# GBprinter-D1-Shield-EXT.net
KiCad netlist of a schematic drawn in EAGLE
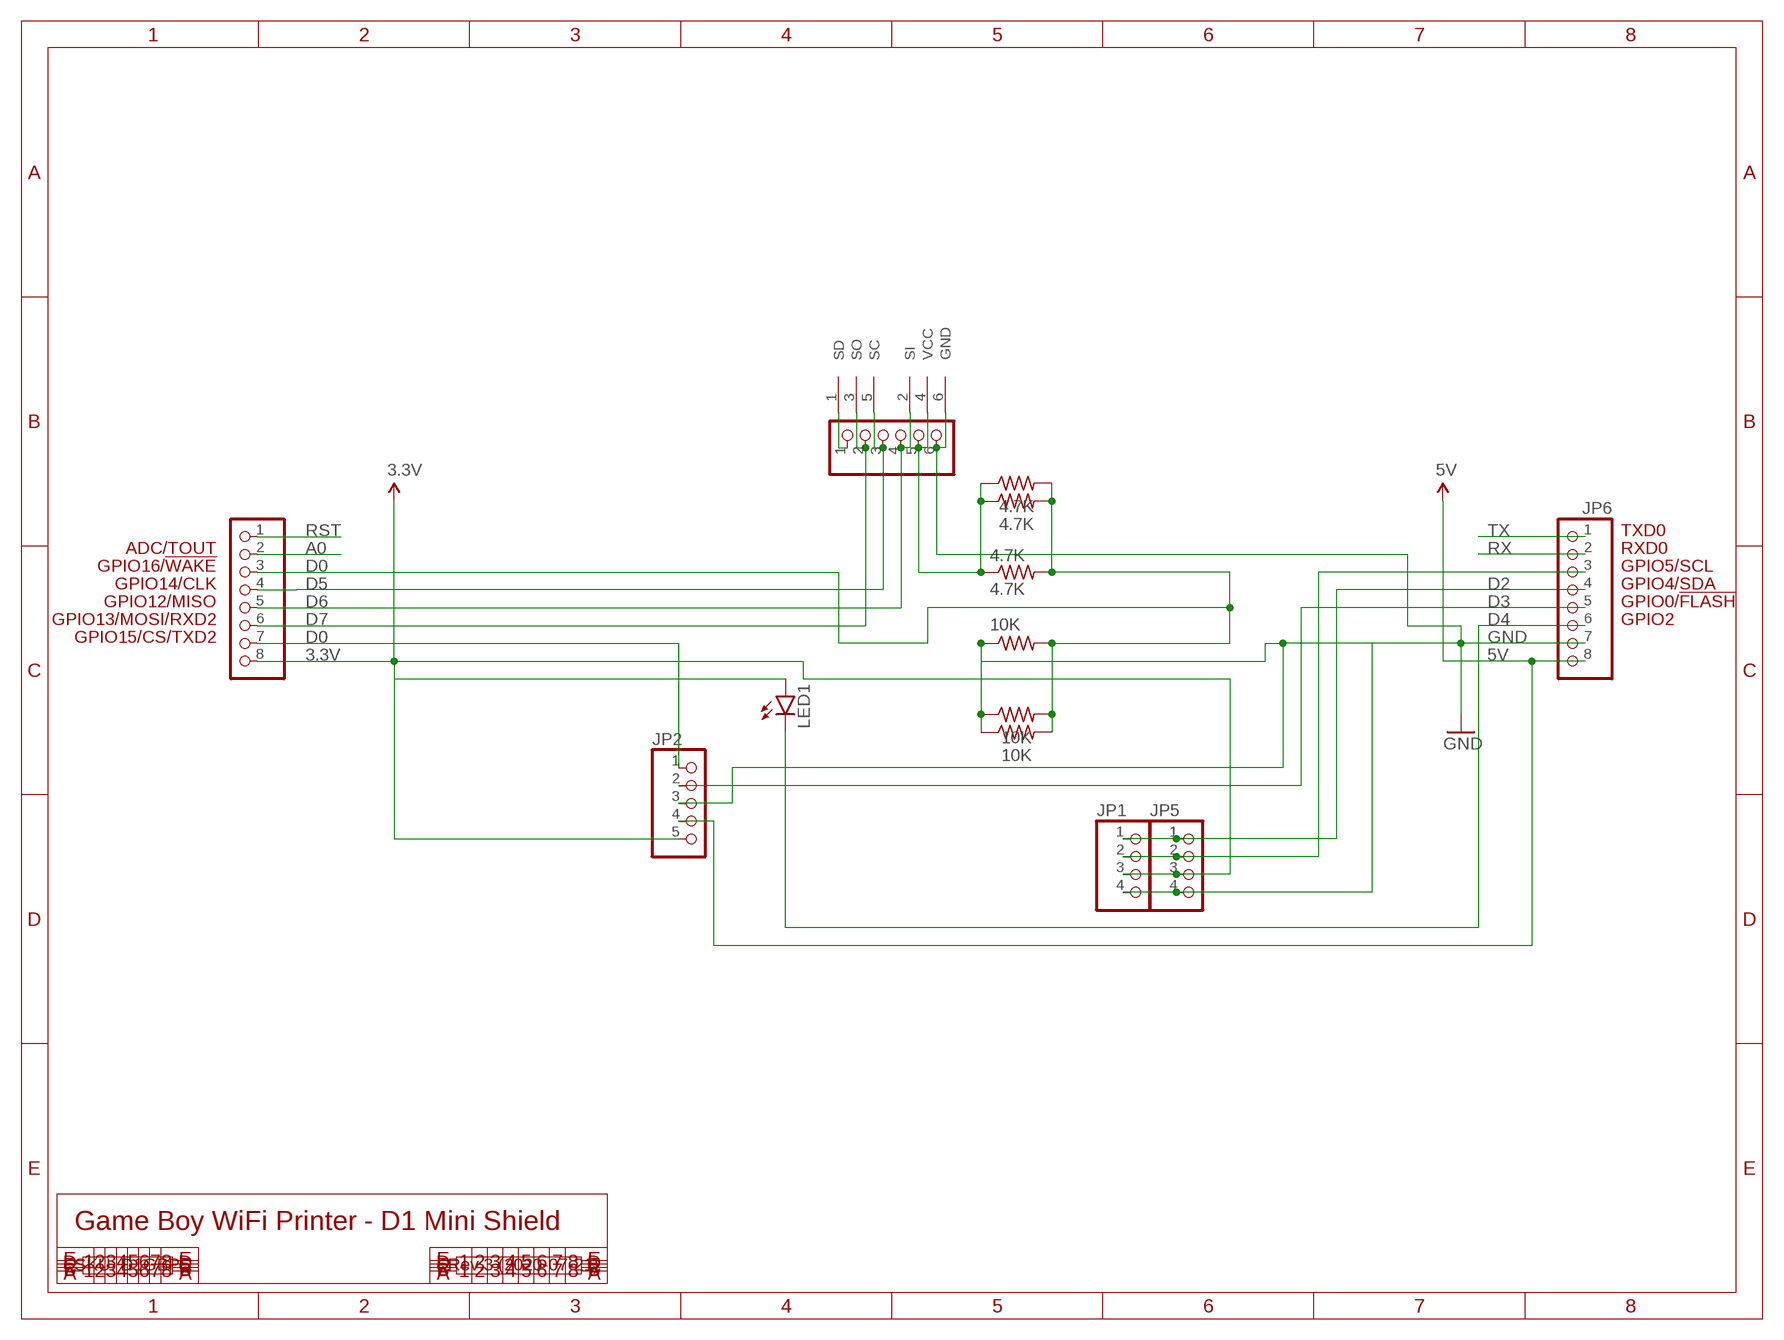
[diagram p0: schematic, sheet 1]

(export (version "E")
  (design (tool "Eeschema 10.0.6"))
  (components
    (comp (ref "4.7K")
      (value "4.7K")
      (footprint "eagle-import:0207_10")
      (libsource (lib "eagle-import") (part "R-US_0207/10"))
    )
    (comp (ref "10K")
      (value "10K")
      (footprint "eagle-import:0207_10")
      (libsource (lib "eagle-import") (part "R-US_0207/10"))
    )
    (comp (ref "JP1")
      (value "PINHD-1X4/OCT")
      (footprint "eagle-import:1X04_OCT")
      (libsource (lib "eagle-import") (part "PINHD-1X4/OCT"))
    )
    (comp (ref "JP2")
      (value "PINHD-1X5/OCT")
      (footprint "eagle-import:1X05_OCT")
      (libsource (lib "eagle-import") (part "PINHD-1X5/OCT"))
    )
    (comp (ref "JP3")
      (value "PINHD-1X8/OCT")
      (footprint "eagle-import:1X08_OCT")
      (libsource (lib "eagle-import") (part "PINHD-1X8/OCT"))
    )
    (comp (ref "JP4")
      (value "PINHD-1X6/OCT")
      (footprint "eagle-import:1X06_OCT")
      (libsource (lib "eagle-import") (part "PINHD-1X6/OCT"))
    )
    (comp (ref "JP5")
      (value "PINHD-1X4/OCT")
      (footprint "eagle-import:1X04_OCT")
      (libsource (lib "eagle-import") (part "PINHD-1X4/OCT"))
    )
    (comp (ref "JP6")
      (value "PINHD-1X8/OCT")
      (footprint "eagle-import:1X08_OCT")
      (libsource (lib "eagle-import") (part "PINHD-1X8/OCT"))
    )
    (comp (ref "LED1")
      (value "LED3MM")
      (footprint "eagle-import:LED3MM")
      (libsource (lib "eagle-import") (part "LED3MM"))
    )
    (comp (ref "R1")
      (value "4.7K")
      (footprint "eagle-import:RESC2012X65")
      (libsource (lib "eagle-import") (part "R-USCHIP-0805(2012-METRIC)_"))
    )
    (comp (ref "R2")
      (value "10K")
      (footprint "eagle-import:RESC2012X65")
      (libsource (lib "eagle-import") (part "R-USCHIP-0805(2012-METRIC)_"))
    )
    (comp (ref "R3")
      (value "10K")
      (footprint "eagle-import:RESC2012X65")
      (libsource (lib "eagle-import") (part "R-USCHIP-0805(2012-METRIC)_"))
    )
    (comp (ref "R5")
      (value "4.7K")
      (footprint "eagle-import:RESC2012X65")
      (libsource (lib "eagle-import") (part "R-USCHIP-0805(2012-METRIC)_"))
    )
    (comp (ref "U$2")
      (value "GB-LINK-PADS")
      (footprint "eagle-import:GB-LINK-PCB")
      (libsource (lib "eagle-import") (part "GB-LINK-PADS"))
    )
  )
  (nets
    (net (code "1") (name "/A0") (class "Default")
      (node (ref "JP3") (pin "2") (pinfunction "2_2") (pintype "passive"))
    )
    (net (code "2") (name "/D0") (class "Default")
      (node (ref "10K") (pin "2") (pinfunction "2_2") (pintype "passive"))
      (node (ref "4.7K") (pin "2") (pinfunction "2_2") (pintype "passive"))
      (node (ref "JP3") (pin "3") (pinfunction "3_3") (pintype "passive"))
      (node (ref "R1") (pin "2") (pinfunction "2_2") (pintype "passive"))
      (node (ref "R2") (pin "2") (pinfunction "2_2") (pintype "passive"))
      (node (ref "R3") (pin "2") (pinfunction "2_2") (pintype "passive"))
      (node (ref "R5") (pin "2") (pinfunction "2_2") (pintype "passive"))
    )
    (net (code "3") (name "/D2") (class "Default")
      (node (ref "JP1") (pin "1") (pinfunction "1_1") (pintype "passive"))
      (node (ref "JP5") (pin "1") (pinfunction "1_1") (pintype "passive"))
      (node (ref "JP6") (pin "4") (pinfunction "4_4") (pintype "passive"))
    )
    (net (code "4") (name "/D3") (class "Default")
      (node (ref "JP2") (pin "2") (pinfunction "2_2") (pintype "passive"))
      (node (ref "JP6") (pin "5") (pinfunction "5_5") (pintype "passive"))
    )
    (net (code "5") (name "/D4") (class "Default")
      (node (ref "JP6") (pin "6") (pinfunction "6_6") (pintype "passive"))
      (node (ref "LED1") (pin "K") (pinfunction "C_K") (pintype "passive"))
    )
    (net (code "6") (name "/D5") (class "Default")
      (node (ref "JP3") (pin "4") (pinfunction "4_4") (pintype "passive"))
      (node (ref "JP4") (pin "3") (pinfunction "3_3") (pintype "passive"))
      (node (ref "U$2") (pin "5") (pinfunction "SC_5") (pintype "bidirectional"))
    )
    (net (code "7") (name "/D6") (class "Default")
      (node (ref "JP3") (pin "5") (pinfunction "5_5") (pintype "passive"))
      (node (ref "JP4") (pin "4") (pinfunction "4_4") (pintype "passive"))
      (node (ref "U$2") (pin "2") (pinfunction "SI_2") (pintype "bidirectional"))
    )
    (net (code "8") (name "/D7") (class "Default")
      (node (ref "JP3") (pin "6") (pinfunction "6_6") (pintype "passive"))
      (node (ref "JP4") (pin "2") (pinfunction "2_2") (pintype "passive"))
      (node (ref "U$2") (pin "3") (pinfunction "SO_3") (pintype "bidirectional"))
    )
    (net (code "9") (name "/RST") (class "Default")
      (node (ref "JP3") (pin "1") (pinfunction "1_1") (pintype "passive"))
    )
    (net (code "10") (name "/RX") (class "Default")
      (node (ref "JP6") (pin "2") (pinfunction "2_2") (pintype "passive"))
    )
    (net (code "11") (name "/TX") (class "Default")
      (node (ref "JP6") (pin "1") (pinfunction "1_1") (pintype "passive"))
    )
    (net (code "12") (name "3.3V") (class "Default")
      (node (ref "JP1") (pin "3") (pinfunction "3_3") (pintype "passive"))
      (node (ref "JP2") (pin "5") (pinfunction "5_5") (pintype "passive"))
      (node (ref "JP3") (pin "8") (pinfunction "8_8") (pintype "passive"))
      (node (ref "JP5") (pin "3") (pinfunction "3_3") (pintype "passive"))
      (node (ref "LED1") (pin "A") (pinfunction "A_A") (pintype "passive"))
    )
    (net (code "13") (name "5V") (class "Default")
      (node (ref "JP2") (pin "4") (pinfunction "4_4") (pintype "passive"))
      (node (ref "JP6") (pin "8") (pinfunction "8_8") (pintype "passive"))
    )
    (net (code "14") (name "GND") (class "Default")
      (node (ref "10K") (pin "1") (pinfunction "1_1") (pintype "passive"))
      (node (ref "JP1") (pin "4") (pinfunction "4_4") (pintype "passive"))
      (node (ref "JP2") (pin "3") (pinfunction "3_3") (pintype "passive"))
      (node (ref "JP4") (pin "6") (pinfunction "6_6") (pintype "passive"))
      (node (ref "JP5") (pin "4") (pinfunction "4_4") (pintype "passive"))
      (node (ref "JP6") (pin "7") (pinfunction "7_7") (pintype "passive"))
      (node (ref "R2") (pin "1") (pinfunction "1_1") (pintype "passive"))
      (node (ref "R3") (pin "1") (pinfunction "1_1") (pintype "passive"))
      (node (ref "U$2") (pin "6") (pinfunction "GND_6") (pintype "bidirectional"))
    )
    (net (code "15") (name "Net-(JP1-Pad2)") (class "Default")
      (node (ref "JP1") (pin "2") (pinfunction "2_2") (pintype "passive"))
      (node (ref "JP5") (pin "2") (pinfunction "2_2") (pintype "passive"))
      (node (ref "JP6") (pin "3") (pinfunction "3_3") (pintype "passive"))
    )
    (net (code "16") (name "Net-(JP2-Pad1)") (class "Default")
      (node (ref "JP2") (pin "1") (pinfunction "1_1") (pintype "passive"))
      (node (ref "JP3") (pin "7") (pinfunction "7_7") (pintype "passive"))
    )
    (net (code "17") (name "Net-(U$2-SD)") (class "Default")
      (node (ref "JP4") (pin "1") (pinfunction "1_1") (pintype "passive"))
      (node (ref "U$2") (pin "1") (pinfunction "SD_1") (pintype "bidirectional"))
    )
    (net (code "18") (name "Net-(U$2-VCC)") (class "Default")
      (node (ref "4.7K") (pin "1") (pinfunction "1_1") (pintype "passive"))
      (node (ref "JP4") (pin "5") (pinfunction "5_5") (pintype "passive"))
      (node (ref "R1") (pin "1") (pinfunction "1_1") (pintype "passive"))
      (node (ref "R5") (pin "1") (pinfunction "1_1") (pintype "passive"))
      (node (ref "U$2") (pin "4") (pinfunction "VCC_4") (pintype "bidirectional"))
    )
  )
)
